# Anemometor_ResDiv2.net
KiCad netlist of a schematic drawn in Altium Designer
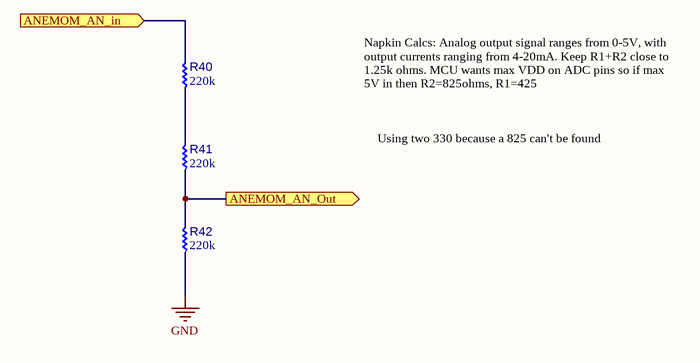
[diagram p0: Anemometor_ResDiv2.SchDoc]

(export (version "E")
  (design (tool "Eeschema 10.0.6"))
  (components
    (comp (ref "R40")
      (value "220k")
      (footprint "New footprint 1")
      (description "Res Thick Film 0603 220K Ohm 1% 0.1W(1/10W) ±100ppm/C Pad SMD Automotive T/R")
      (fields (field (name "TOLERANCE") "1%") (field (name "Comment") "RMCF0603FT220K"))
      (libsource (lib "University of Calgary - SOAR") (part "RES-2"))
    )
    (comp (ref "R41")
      (value "220k")
      (footprint "New footprint 1")
      (description "Res Thick Film 0603 220K Ohm 1% 0.1W(1/10W) ±100ppm/C Pad SMD Automotive T/R")
      (fields (field (name "TOLERANCE") "1%") (field (name "Comment") "RMCF0603FT220K"))
      (libsource (lib "University of Calgary - SOAR") (part "RES-2"))
    )
    (comp (ref "R42")
      (value "220k")
      (footprint "New footprint 1")
      (description "Res Thick Film 0603 220K Ohm 1% 0.1W(1/10W) ±100ppm/C Pad SMD Automotive T/R")
      (fields (field (name "TOLERANCE") "1%") (field (name "Comment") "RMCF0603FT220K"))
      (libsource (lib "University of Calgary - SOAR") (part "RES-2"))
    )
  )
  (nets
    (net (code "1") (name "/ANEMOM_AN_Out") (class "Default")
      (node (ref "R41") (pin "1") (pinfunction "1_1") (pintype "passive"))
      (node (ref "R42") (pin "2") (pinfunction "2_2") (pintype "passive"))
    )
    (net (code "2") (name "/ANEMOM_AN_in") (class "Default")
      (node (ref "R40") (pin "2") (pinfunction "2_2") (pintype "passive"))
    )
    (net (code "3") (name "GND") (class "Default")
      (node (ref "R42") (pin "1") (pinfunction "1_1") (pintype "passive"))
    )
    (net (code "4") (name "Net-(R40-Pad1)") (class "Default")
      (node (ref "R40") (pin "1") (pinfunction "1_1") (pintype "passive"))
      (node (ref "R41") (pin "2") (pinfunction "2_2") (pintype "passive"))
    )
  )
)
